# RefOsc10MHz_2V0.net
KiCad netlist of a schematic drawn in EAGLE
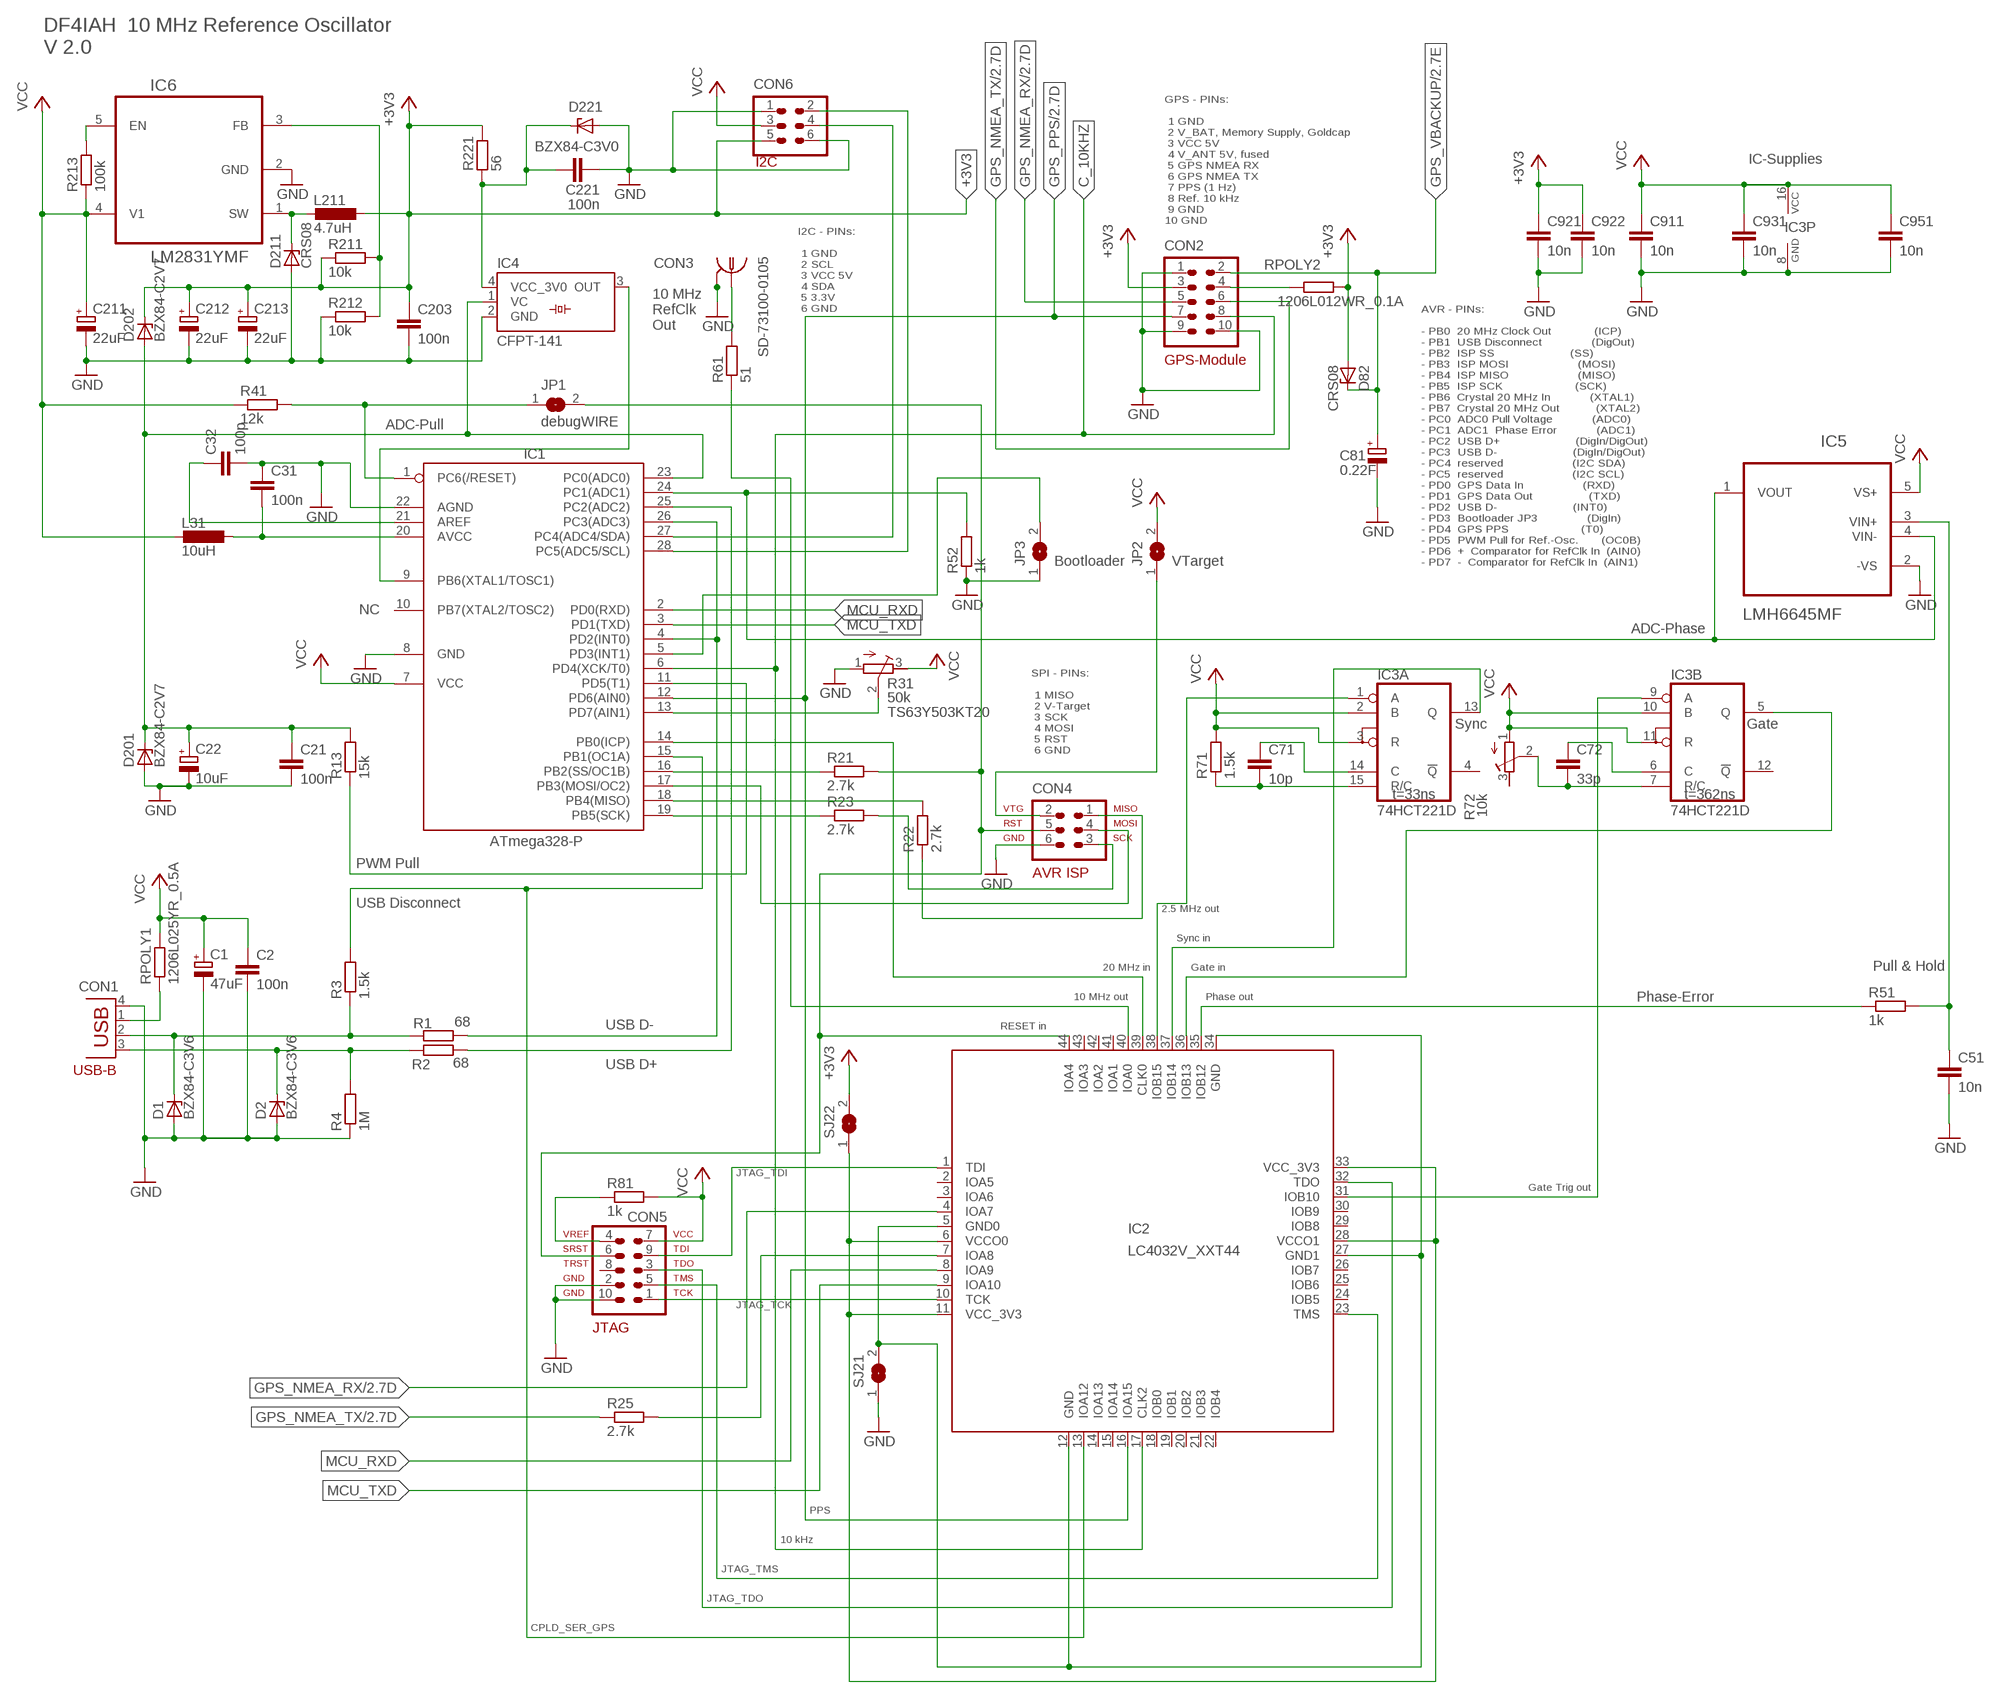
[diagram p0: schematic, sheet 1]
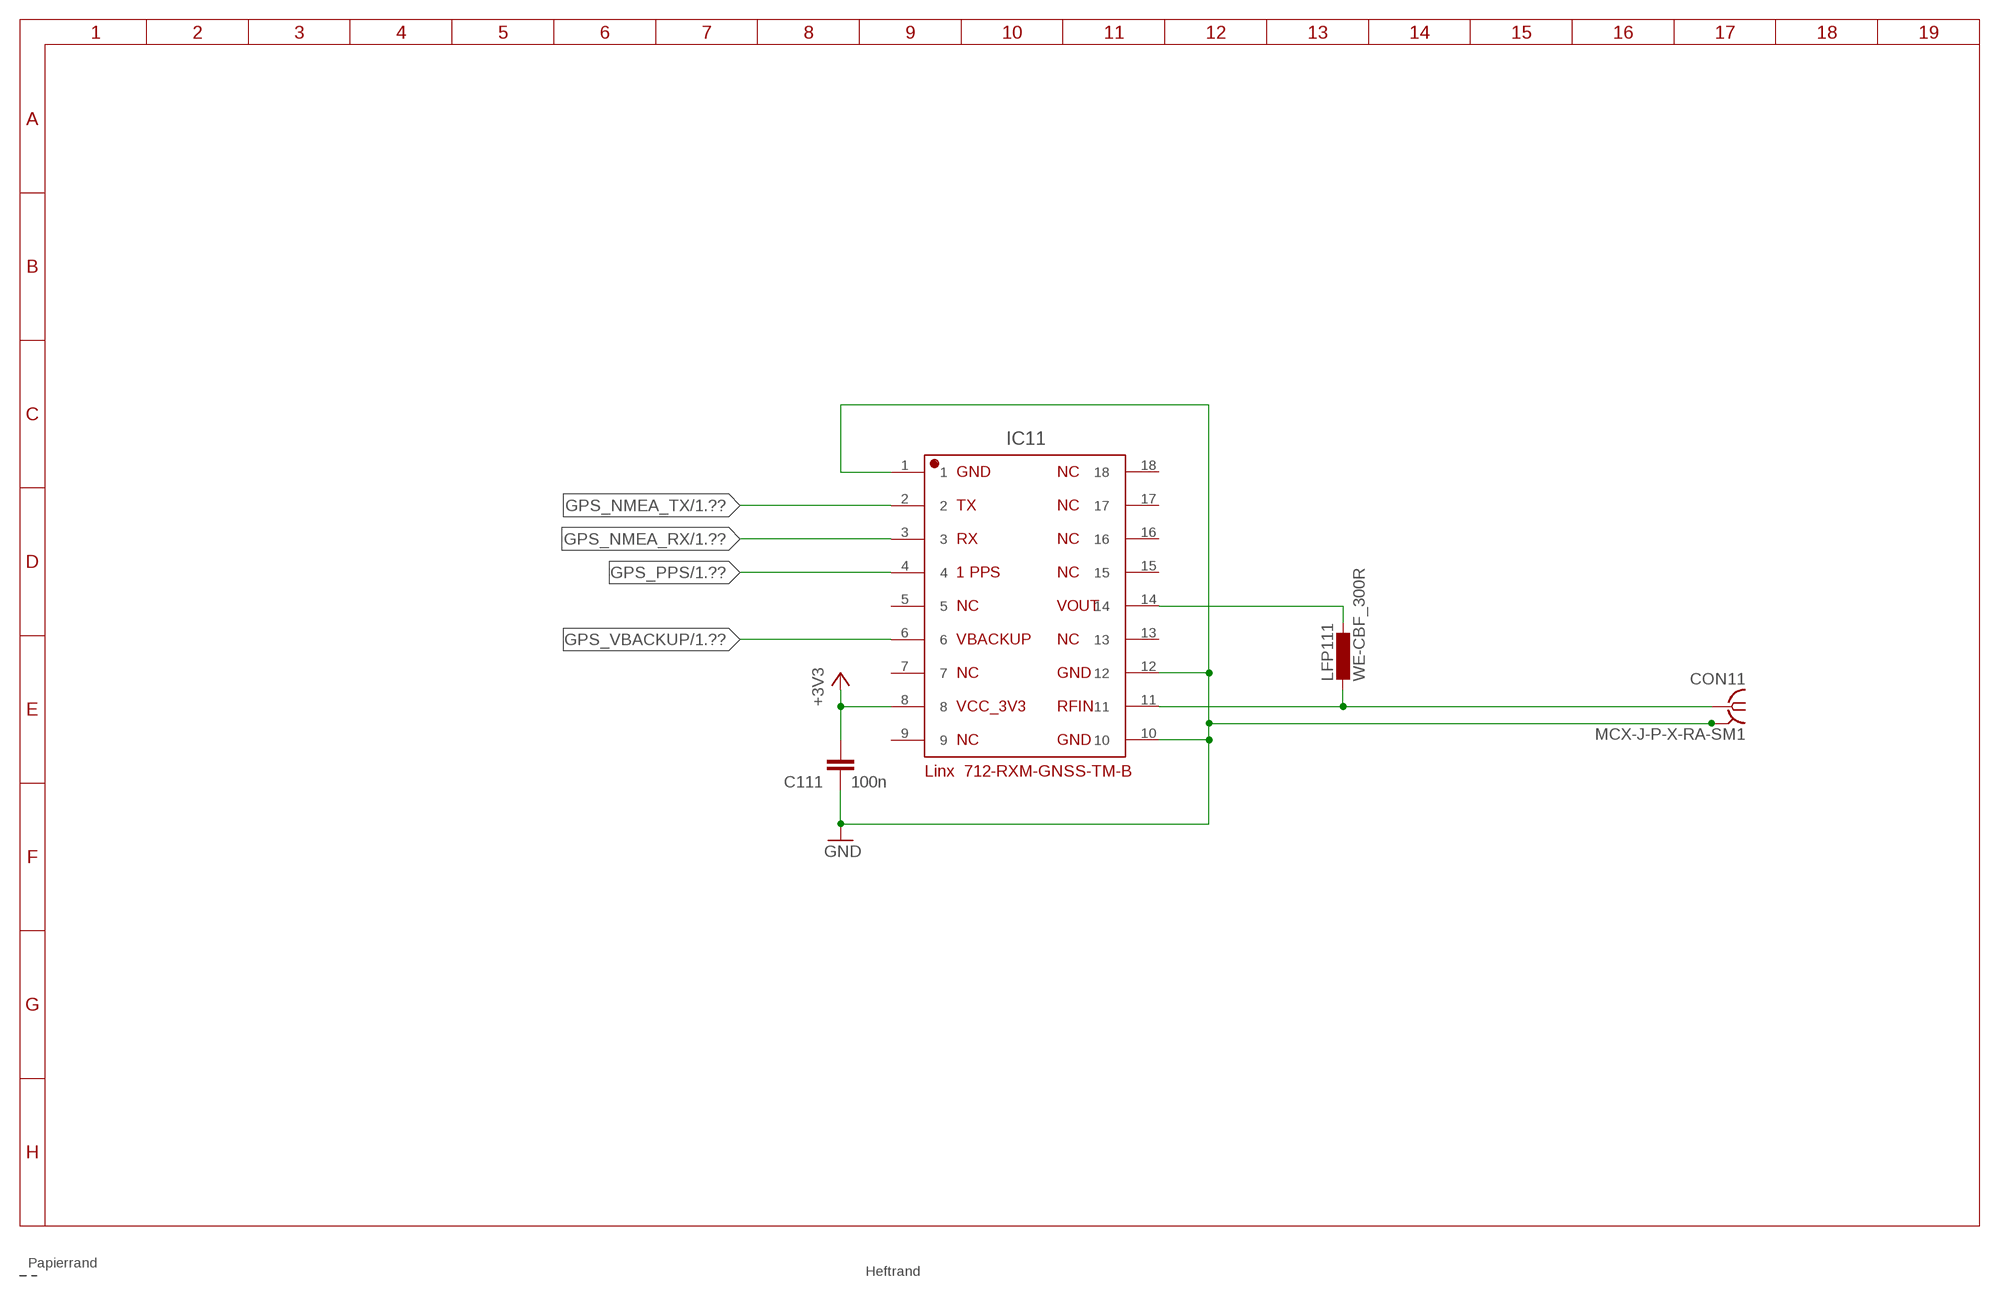
[diagram p1: schematic, sheet 2]

(export (version "E")
  (design (tool "Eeschema 10.0.6"))
  (components
    (comp (ref "C1")
      (value "47uF")
      (footprint "eagle-import:PANASONIC_C")
      (libsource (lib "eagle-import") (part "CPOL-EUC"))
    )
    (comp (ref "C2")
      (value "100n")
      (footprint "eagle-import:C0805")
      (libsource (lib "eagle-import") (part "rcl_C-EUC0805"))
    )
    (comp (ref "C21")
      (value "100n")
      (footprint "eagle-import:C0805")
      (libsource (lib "eagle-import") (part "rcl_C-EUC0805"))
    )
    (comp (ref "C22")
      (value "10uF")
      (footprint "eagle-import:PANASONIC_B")
      (libsource (lib "eagle-import") (part "CPOL-EUB"))
    )
    (comp (ref "C31")
      (value "100n")
      (footprint "eagle-import:C0805")
      (libsource (lib "eagle-import") (part "rcl_C-EUC0805"))
    )
    (comp (ref "C32")
      (value "100p")
      (footprint "eagle-import:C0805")
      (libsource (lib "eagle-import") (part "rcl_C-EUC0805"))
    )
    (comp (ref "C51")
      (value "10n")
      (footprint "eagle-import:C0805")
      (libsource (lib "eagle-import") (part "rcl_C-EUC0805"))
    )
    (comp (ref "C71")
      (value "10p")
      (footprint "eagle-import:C0805")
      (libsource (lib "eagle-import") (part "rcl_C-EUC0805"))
    )
    (comp (ref "C72")
      (value "33p")
      (footprint "eagle-import:C0805")
      (libsource (lib "eagle-import") (part "rcl_C-EUC0805"))
    )
    (comp (ref "C81")
      (value "0.22F")
      (footprint "eagle-import:PANASONIC_C")
      (libsource (lib "eagle-import") (part "CPOL-EUC"))
    )
    (comp (ref "C203")
      (value "100n")
      (footprint "eagle-import:C0805")
      (libsource (lib "eagle-import") (part "rcl_C-EUC0805"))
    )
    (comp (ref "C211")
      (value "22uF")
      (footprint "eagle-import:A_3216-18W")
      (libsource (lib "eagle-import") (part "CPOL-EUA/3216-18W"))
    )
    (comp (ref "C212")
      (value "22uF")
      (footprint "eagle-import:A_3216-18W")
      (libsource (lib "eagle-import") (part "CPOL-EUA/3216-18W"))
    )
    (comp (ref "C213")
      (value "22uF")
      (footprint "eagle-import:A_3216-18W")
      (libsource (lib "eagle-import") (part "CPOL-EUA/3216-18W"))
    )
    (comp (ref "C221")
      (value "100n")
      (footprint "eagle-import:C0805")
      (libsource (lib "eagle-import") (part "rcl_C-EUC0805"))
    )
    (comp (ref "C911")
      (value "10n")
      (footprint "eagle-import:C0805")
      (libsource (lib "eagle-import") (part "rcl_C-EUC0805"))
    )
    (comp (ref "C921")
      (value "10n")
      (footprint "eagle-import:C0805")
      (libsource (lib "eagle-import") (part "rcl_C-EUC0805"))
    )
    (comp (ref "C922")
      (value "10n")
      (footprint "eagle-import:C0805")
      (libsource (lib "eagle-import") (part "rcl_C-EUC0805"))
    )
    (comp (ref "C931")
      (value "10n")
      (footprint "eagle-import:C0805")
      (libsource (lib "eagle-import") (part "rcl_C-EUC0805"))
    )
    (comp (ref "C951")
      (value "10n")
      (footprint "eagle-import:C0805")
      (libsource (lib "eagle-import") (part "rcl_C-EUC0805"))
    )
    (comp (ref "CON1")
      (value "TYCO-AMP_USBUSB-B_SMT")
      (footprint "eagle-import:TYCO-AMP_USB-B_SMT")
      (fields (field (name "MF") "TYCO-AMP") (field (name "MPN") "1734346"))
      (libsource (lib "eagle-import") (part "TYCO-AMP_USBUSB-B_SMT"))
    )
    (comp (ref "CON2")
      (value "HEADER-2X5SMD")
      (footprint "eagle-import:2X5SMD")
      (libsource (lib "eagle-import") (part "HEADER-2X5SMD"))
    )
    (comp (ref "CON3")
      (value "SD-73100-0105")
      (footprint "eagle-import:MOLEX_BNC-JACK-50R_SD-73100-0105")
      (fields (field (name "MF") "MOLEX"))
      (libsource (lib "eagle-import") (part "MOLEX_BNC-JACK-50R_SD-73100-0105"))
    )
    (comp (ref "CON4")
      (value "AVR-ISP-6SMD")
      (footprint "eagle-import:2X3SMD")
      (libsource (lib "eagle-import") (part "AVR-ISP-6SMD"))
    )
    (comp (ref "CON5")
      (value "AVR-JTAG-10SMD")
      (footprint "eagle-import:2X5SMD")
      (libsource (lib "eagle-import") (part "AVR-JTAG-10SMD"))
    )
    (comp (ref "CON6")
      (value "HEADER-2X3SMD")
      (footprint "eagle-import:2X03SMD")
      (libsource (lib "eagle-import") (part "HEADER-2X3SMD"))
    )
    (comp (ref "D1")
      (value "BZX84-C3V6")
      (footprint "eagle-import:TO236")
      (libsource (lib "eagle-import") (part "BZX84CSMD"))
    )
    (comp (ref "D2")
      (value "BZX84-C3V6")
      (footprint "eagle-import:TO236")
      (libsource (lib "eagle-import") (part "BZX84CSMD"))
    )
    (comp (ref "D82")
      (value "CRS08")
      (footprint "eagle-import:SOT23")
      (libsource (lib "eagle-import") (part "ZENER-DIODESOT23"))
    )
    (comp (ref "D201")
      (value "BZX84-C2V7")
      (footprint "eagle-import:TO236")
      (libsource (lib "eagle-import") (part "BZX84CSMD"))
    )
    (comp (ref "D202")
      (value "BZX84-C2V7")
      (footprint "eagle-import:TO236")
      (libsource (lib "eagle-import") (part "BZX84CSMD"))
    )
    (comp (ref "D211")
      (value "CRS08")
      (footprint "eagle-import:SOT23")
      (libsource (lib "eagle-import") (part "ZENER-DIODESOT23"))
    )
    (comp (ref "D221")
      (value "BZX84-C3V0")
      (footprint "eagle-import:TO236")
      (libsource (lib "eagle-import") (part "BZX84CSMD"))
    )
    (comp (ref "IC1")
      (value "ATmega328-P")
      (footprint "eagle-import:DIL28-3")
      (libsource (lib "eagle-import") (part "MEGA8-P"))
    )
    (comp (ref "IC2")
      (value "LC4032V_XXT44")
      (footprint "eagle-import:TQFP44")
      (libsource (lib "eagle-import") (part "LC4032V_XXT44"))
    )
    (comp (ref "IC3")
      (value "74HCT221D")
      (footprint "eagle-import:SO16")
      (libsource (lib "eagle-import") (part "74221DHCT"))
    )
    (comp (ref "IC4")
      (value "CFPT-141")
      (footprint "eagle-import:CFPT-141")
      (fields (field (name "MF") "IQD-FREQUENCY-PRODUCTS") (field (name "MPN") "LFTVXO022175"))
      (libsource (lib "eagle-import") (part "CFPT-141"))
    )
    (comp (ref "IC5")
      (value "LMH6645MF")
      (footprint "eagle-import:SOT95P280X145-5N")
      (libsource (lib "eagle-import") (part "LMH6645MF"))
    )
    (comp (ref "IC6")
      (value "LM2831YMF")
      (footprint "eagle-import:SOT95P280X145-5N")
      (fields (field (name "MPN") "LM2831YMF/NOPB"))
      (libsource (lib "eagle-import") (part "LM2831YMF"))
    )
    (comp (ref "JP1")
      (value "SJW")
      (footprint "eagle-import:SJW")
      (libsource (lib "eagle-import") (part "SJW"))
    )
    (comp (ref "JP2")
      (value "SJW")
      (footprint "eagle-import:SJW")
      (libsource (lib "eagle-import") (part "SJW"))
    )
    (comp (ref "JP3")
      (value "SJW")
      (footprint "eagle-import:SJW")
      (libsource (lib "eagle-import") (part "SJW"))
    )
    (comp (ref "L31")
      (value "10uH")
      (footprint "eagle-import:L1812")
      (libsource (lib "eagle-import") (part "rcl_L-EUL1812"))
    )
    (comp (ref "L211")
      (value "4.7uH")
      (footprint "eagle-import:L5650M")
      (libsource (lib "eagle-import") (part "rcl_L-EUL5650M"))
    )
    (comp (ref "R1")
      (value "68")
      (footprint "eagle-import:R0805")
      (libsource (lib "eagle-import") (part "R-EU_R0805"))
    )
    (comp (ref "R2")
      (value "68")
      (footprint "eagle-import:R0805")
      (libsource (lib "eagle-import") (part "R-EU_R0805"))
    )
    (comp (ref "R3")
      (value "1.5k")
      (footprint "eagle-import:R0805")
      (libsource (lib "eagle-import") (part "R-EU_R0805"))
    )
    (comp (ref "R4")
      (value "1M")
      (footprint "eagle-import:R0805")
      (libsource (lib "eagle-import") (part "R-EU_R0805"))
    )
    (comp (ref "R13")
      (value "15k")
      (footprint "eagle-import:R0805")
      (libsource (lib "eagle-import") (part "R-EU_R0805"))
    )
    (comp (ref "R21")
      (value "2.7k")
      (footprint "eagle-import:R0805")
      (libsource (lib "eagle-import") (part "R-EU_R0805"))
    )
    (comp (ref "R22")
      (value "2.7k")
      (footprint "eagle-import:R0805")
      (libsource (lib "eagle-import") (part "R-EU_R0805"))
    )
    (comp (ref "R23")
      (value "2.7k")
      (footprint "eagle-import:R0805")
      (libsource (lib "eagle-import") (part "R-EU_R0805"))
    )
    (comp (ref "R25")
      (value "2.7k")
      (footprint "eagle-import:R0805")
      (libsource (lib "eagle-import") (part "R-EU_R0805"))
    )
    (comp (ref "R31")
      (value "50k")
      (footprint "eagle-import:RTRIMTS63Y")
      (fields (field (name "NR") "TS63Y503KT20"))
      (libsource (lib "eagle-import") (part "R-TRIMMTS63Y"))
    )
    (comp (ref "R41")
      (value "12k")
      (footprint "eagle-import:R0805")
      (libsource (lib "eagle-import") (part "R-EU_R0805"))
    )
    (comp (ref "R51")
      (value "1k")
      (footprint "eagle-import:R0805")
      (libsource (lib "eagle-import") (part "R-EU_R0805"))
    )
    (comp (ref "R52")
      (value "1k")
      (footprint "eagle-import:R0805")
      (libsource (lib "eagle-import") (part "R-EU_R0805"))
    )
    (comp (ref "R61")
      (value "51")
      (footprint "eagle-import:R0805")
      (libsource (lib "eagle-import") (part "R-EU_R0805"))
    )
    (comp (ref "R71")
      (value "1.5k")
      (footprint "eagle-import:R0805")
      (libsource (lib "eagle-import") (part "R-EU_R0805"))
    )
    (comp (ref "R72")
      (value "10k")
      (footprint "eagle-import:RTRIMTS63Y")
      (libsource (lib "eagle-import") (part "R-TRIMMTS63Y"))
    )
    (comp (ref "R81")
      (value "1k")
      (footprint "eagle-import:R0805")
      (libsource (lib "eagle-import") (part "R-EU_R0805"))
    )
    (comp (ref "R211")
      (value "10k")
      (footprint "eagle-import:R0805")
      (libsource (lib "eagle-import") (part "R-EU_R0805"))
    )
    (comp (ref "R212")
      (value "10k")
      (footprint "eagle-import:R0805")
      (libsource (lib "eagle-import") (part "R-EU_R0805"))
    )
    (comp (ref "R213")
      (value "100k")
      (footprint "eagle-import:R0805")
      (libsource (lib "eagle-import") (part "R-EU_R0805"))
    )
    (comp (ref "R221")
      (value "56")
      (footprint "eagle-import:R0805")
      (libsource (lib "eagle-import") (part "R-EU_R0805"))
    )
    (comp (ref "RPOLY1")
      (value "1206L025YR_0.5A")
      (footprint "eagle-import:M1206")
      (libsource (lib "eagle-import") (part "R-EU_M1206"))
    )
    (comp (ref "RPOLY2")
      (value "1206L012WR_0.1A")
      (footprint "eagle-import:M1206")
      (libsource (lib "eagle-import") (part "R-EU_M1206"))
    )
    (comp (ref "SJ21")
      (value "SJ")
      (footprint "eagle-import:SJ")
      (libsource (lib "eagle-import") (part "SJ"))
    )
    (comp (ref "SJ22")
      (value "SJ")
      (footprint "eagle-import:SJ")
      (libsource (lib "eagle-import") (part "SJ"))
    )
    (comp (ref "C111")
      (value "100n")
      (footprint "eagle-import:C0805")
      (libsource (lib "eagle-import") (part "C-EUC0805"))
    )
    (comp (ref "CON11")
      (value "MCX-J-P-X-RA-SM1")
      (footprint "eagle-import:MCX-J-P-X-RA-SM1")
      (libsource (lib "eagle-import") (part "MCX-J-P-X-RA-SM1"))
    )
    (comp (ref "IC11")
      (value "712-RXM-GNSS-TM-B")
      (footprint "eagle-import:712-RXM-GNSS-TM-B")
      (libsource (lib "eagle-import") (part "712-RXM-GNSS-TM-B"))
    )
    (comp (ref "LFP111")
      (value "WE-CBF_300R")
      (footprint "eagle-import:L3216C")
      (libsource (lib "eagle-import") (part "L-EUL3216C"))
    )
  )
  (nets
    (net (code "1") (name "+3V3") (class "Default")
      (node (ref "C111") (pin "1") (pinfunction "1_1") (pintype "passive"))
      (node (ref "C203") (pin "1") (pinfunction "1_1") (pintype "passive"))
      (node (ref "C212") (pin "+") (pinfunction "+_+") (pintype "passive"))
      (node (ref "C213") (pin "+") (pinfunction "+_+") (pintype "passive"))
      (node (ref "C921") (pin "1") (pinfunction "1_1") (pintype "passive"))
      (node (ref "C922") (pin "1") (pinfunction "1_1") (pintype "passive"))
      (node (ref "CON2") (pin "3") (pinfunction "3_3") (pintype "passive"))
      (node (ref "CON6") (pin "5") (pinfunction "5_5") (pintype "passive"))
      (node (ref "D202") (pin "C") (pinfunction "C_C") (pintype "passive"))
      (node (ref "D82") (pin "1") (pinfunction "A_1") (pintype "passive"))
      (node (ref "IC11") (pin "8") (pinfunction "8_8") (pintype "power_in"))
      (node (ref "L211") (pin "1") (pinfunction "1_1") (pintype "passive"))
      (node (ref "R211") (pin "1") (pinfunction "1_1") (pintype "passive"))
      (node (ref "R221") (pin "1") (pinfunction "1_1") (pintype "passive"))
      (node (ref "RPOLY2") (pin "2") (pinfunction "2_2") (pintype "passive"))
      (node (ref "SJ22") (pin "2") (pinfunction "2_2") (pintype "passive"))
    )
    (net (code "2") (name "C_10KHZ") (class "Default")
      (node (ref "CON2") (pin "8") (pinfunction "8_8") (pintype "passive"))
      (node (ref "IC1") (pin "6") (pinfunction "PD4(XCK/T0)_6") (pintype "bidirectional"))
      (node (ref "IC2") (pin "17") (pinfunction "CLK2_17") (pintype "input"))
    )
    (net (code "3") (name "GND") (class "Default")
      (node (ref "C1") (pin "-") (pinfunction "-_-") (pintype "passive"))
      (node (ref "C111") (pin "2") (pinfunction "2_2") (pintype "passive"))
      (node (ref "C2") (pin "2") (pinfunction "2_2") (pintype "passive"))
      (node (ref "C203") (pin "2") (pinfunction "2_2") (pintype "passive"))
      (node (ref "C21") (pin "2") (pinfunction "2_2") (pintype "passive"))
      (node (ref "C211") (pin "-") (pinfunction "-_-") (pintype "passive"))
      (node (ref "C212") (pin "-") (pinfunction "-_-") (pintype "passive"))
      (node (ref "C213") (pin "-") (pinfunction "-_-") (pintype "passive"))
      (node (ref "C22") (pin "-") (pinfunction "-_-") (pintype "passive"))
      (node (ref "C221") (pin "2") (pinfunction "2_2") (pintype "passive"))
      (node (ref "C31") (pin "1") (pinfunction "1_1") (pintype "passive"))
      (node (ref "C32") (pin "2") (pinfunction "2_2") (pintype "passive"))
      (node (ref "C51") (pin "2") (pinfunction "2_2") (pintype "passive"))
      (node (ref "C81") (pin "-") (pinfunction "-_-") (pintype "passive"))
      (node (ref "C911") (pin "2") (pinfunction "2_2") (pintype "passive"))
      (node (ref "C921") (pin "2") (pinfunction "2_2") (pintype "passive"))
      (node (ref "C922") (pin "2") (pinfunction "2_2") (pintype "passive"))
      (node (ref "C931") (pin "2") (pinfunction "2_2") (pintype "passive"))
      (node (ref "C951") (pin "2") (pinfunction "2_2") (pintype "passive"))
      (node (ref "CON1") (pin "4") (pinfunction "GND_4") (pintype "bidirectional"))
      (node (ref "CON11") (pin "2") (pinfunction "2_2") (pintype "passive"))
      (node (ref "CON11") (pin "3") (pinfunction "3_3") (pintype "passive"))
      (node (ref "CON11") (pin "4") (pinfunction "4_4") (pintype "passive"))
      (node (ref "CON11") (pin "5") (pinfunction "5_5") (pintype "passive"))
      (node (ref "CON2") (pin "1") (pinfunction "1_1") (pintype "passive"))
      (node (ref "CON2") (pin "10") (pinfunction "10_10") (pintype "passive"))
      (node (ref "CON2") (pin "9") (pinfunction "9_9") (pintype "passive"))
      (node (ref "CON3") (pin "2") (pinfunction "2_2") (pintype "passive"))
      (node (ref "CON3") (pin "3") (pinfunction "3_3") (pintype "passive"))
      (node (ref "CON4") (pin "6") (pinfunction "6_6") (pintype "passive"))
      (node (ref "CON5") (pin "10") (pinfunction "10_10") (pintype "passive"))
      (node (ref "CON5") (pin "2") (pinfunction "2_2") (pintype "passive"))
      (node (ref "CON6") (pin "1") (pinfunction "1_1") (pintype "passive"))
      (node (ref "CON6") (pin "6") (pinfunction "6_6") (pintype "passive"))
      (node (ref "D1") (pin "A") (pinfunction "A_A") (pintype "passive"))
      (node (ref "D2") (pin "A") (pinfunction "A_A") (pintype "passive"))
      (node (ref "D201") (pin "A") (pinfunction "A_A") (pintype "passive"))
      (node (ref "D211") (pin "1") (pinfunction "A_1") (pintype "passive"))
      (node (ref "D221") (pin "A") (pinfunction "A_A") (pintype "passive"))
      (node (ref "IC1") (pin "22") (pinfunction "AGND_22") (pintype "bidirectional"))
      (node (ref "IC1") (pin "8") (pinfunction "GND_8") (pintype "bidirectional"))
      (node (ref "IC11") (pin "1") (pinfunction "1_1") (pintype "power_in"))
      (node (ref "IC11") (pin "10") (pinfunction "10_10") (pintype "power_in"))
      (node (ref "IC11") (pin "12") (pinfunction "12_12") (pintype "power_in"))
      (node (ref "IC3") (pin "8") (pinfunction "GND_8") (pintype "power_in"))
      (node (ref "IC4") (pin "2") (pinfunction "GND_2") (pintype "power_in"))
      (node (ref "IC5") (pin "2") (pinfunction "-VS_2") (pintype "power_in"))
      (node (ref "IC6") (pin "2") (pinfunction "GND_2") (pintype "power_in"))
      (node (ref "JP3") (pin "1") (pinfunction "1_1") (pintype "passive"))
      (node (ref "R212") (pin "1") (pinfunction "1_1") (pintype "passive"))
      (node (ref "R31") (pin "1") (pinfunction "A_1") (pintype "passive"))
      (node (ref "R4") (pin "1") (pinfunction "1_1") (pintype "passive"))
      (node (ref "R52") (pin "1") (pinfunction "1_1") (pintype "passive"))
      (node (ref "SJ21") (pin "1") (pinfunction "1_1") (pintype "passive"))
    )
    (net (code "4") (name "GPS_NMEA_RX") (class "Default")
      (node (ref "CON2") (pin "5") (pinfunction "5_5") (pintype "passive"))
      (node (ref "IC11") (pin "3") (pinfunction "3_3") (pintype "output"))
      (node (ref "IC2") (pin "4") (pinfunction "IOA7_4") (pintype "bidirectional"))
    )
    (net (code "5") (name "GPS_NMEA_TX") (class "Default")
      (node (ref "CON2") (pin "6") (pinfunction "6_6") (pintype "passive"))
      (node (ref "IC11") (pin "2") (pinfunction "2_2") (pintype "input"))
      (node (ref "R25") (pin "1") (pinfunction "1_1") (pintype "passive"))
    )
    (net (code "6") (name "GPS_PPS") (class "Default")
      (node (ref "CON2") (pin "7") (pinfunction "7_7") (pintype "passive"))
      (node (ref "IC1") (pin "12") (pinfunction "PD6(AIN0)_12") (pintype "bidirectional"))
      (node (ref "IC11") (pin "4") (pinfunction "4_4") (pintype "output"))
      (node (ref "IC2") (pin "16") (pinfunction "IOA15_16") (pintype "bidirectional"))
    )
    (net (code "7") (name "GPS_VBACKUP") (class "Default")
      (node (ref "C81") (pin "+") (pinfunction "+_+") (pintype "passive"))
      (node (ref "CON2") (pin "2") (pinfunction "2_2") (pintype "passive"))
      (node (ref "D82") (pin "3") (pinfunction "C_3") (pintype "passive"))
      (node (ref "IC11") (pin "6") (pinfunction "6_6") (pintype "power_in"))
    )
    (net (code "8") (name "MCU_RXD") (class "Default")
      (node (ref "IC1") (pin "2") (pinfunction "PD0(RXD)_2") (pintype "bidirectional"))
      (node (ref "IC2") (pin "8") (pinfunction "IOA9_8") (pintype "bidirectional"))
    )
    (net (code "9") (name "MCU_TXD") (class "Default")
      (node (ref "IC1") (pin "3") (pinfunction "PD1(TXD)_3") (pintype "bidirectional"))
      (node (ref "IC2") (pin "9") (pinfunction "IOA10_9") (pintype "bidirectional"))
    )
    (net (code "10") (name "Net-(CON1-D+)") (class "Default")
      (node (ref "CON1") (pin "3") (pinfunction "D+_3") (pintype "bidirectional"))
      (node (ref "D2") (pin "C") (pinfunction "C_C") (pintype "passive"))
      (node (ref "R2") (pin "1") (pinfunction "1_1") (pintype "passive"))
      (node (ref "R4") (pin "2") (pinfunction "2_2") (pintype "passive"))
    )
    (net (code "11") (name "Net-(CON1-D-)") (class "Default")
      (node (ref "CON1") (pin "2") (pinfunction "D-_2") (pintype "bidirectional"))
      (node (ref "D1") (pin "C") (pinfunction "C_C") (pintype "passive"))
      (node (ref "R1") (pin "1") (pinfunction "1_1") (pintype "passive"))
      (node (ref "R3") (pin "1") (pinfunction "1_1") (pintype "passive"))
    )
    (net (code "12") (name "Net-(CON1-VBUS)") (class "Default")
      (node (ref "CON1") (pin "1") (pinfunction "VBUS_1") (pintype "bidirectional"))
      (node (ref "RPOLY1") (pin "1") (pinfunction "1_1") (pintype "passive"))
    )
    (net (code "13") (name "Net-(CON2-Pad4)") (class "Default")
      (node (ref "CON2") (pin "4") (pinfunction "4_4") (pintype "passive"))
      (node (ref "RPOLY2") (pin "1") (pinfunction "1_1") (pintype "passive"))
    )
    (net (code "14") (name "Net-(CON3-Pad1)") (class "Default")
      (node (ref "CON3") (pin "1") (pinfunction "1_1") (pintype "passive"))
      (node (ref "R61") (pin "2") (pinfunction "2_2") (pintype "passive"))
    )
    (net (code "15") (name "Net-(CON4-Pad1)") (class "Default")
      (node (ref "CON4") (pin "1") (pinfunction "1_1") (pintype "passive"))
      (node (ref "R22") (pin "1") (pinfunction "1_1") (pintype "passive"))
    )
    (net (code "16") (name "Net-(CON4-Pad2)") (class "Default")
      (node (ref "CON4") (pin "2") (pinfunction "2_2") (pintype "passive"))
      (node (ref "JP2") (pin "1") (pinfunction "1_1") (pintype "passive"))
    )
    (net (code "17") (name "Net-(CON4-Pad3)") (class "Default")
      (node (ref "CON4") (pin "3") (pinfunction "3_3") (pintype "passive"))
      (node (ref "R23") (pin "2") (pinfunction "2_2") (pintype "passive"))
    )
    (net (code "18") (name "Net-(CON5-Pad4)") (class "Default")
      (node (ref "CON5") (pin "4") (pinfunction "4_4") (pintype "passive"))
      (node (ref "R81") (pin "1") (pinfunction "1_1") (pintype "passive"))
    )
    (net (code "19") (name "Net-(CON11-Pad1)") (class "Default")
      (node (ref "CON11") (pin "1") (pinfunction "1_1") (pintype "passive"))
      (node (ref "IC11") (pin "11") (pinfunction "11_11") (pintype "input"))
      (node (ref "LFP111") (pin "2") (pinfunction "2_2") (pintype "passive"))
    )
    (net (code "20") (name "Net-(D211-C)") (class "Default")
      (node (ref "D211") (pin "3") (pinfunction "C_3") (pintype "passive"))
      (node (ref "IC6") (pin "1") (pinfunction "SW_1") (pintype "output"))
      (node (ref "L211") (pin "2") (pinfunction "2_2") (pintype "passive"))
    )
    (net (code "21") (name "Net-(IC1-AREF)") (class "Default")
      (node (ref "C32") (pin "1") (pinfunction "1_1") (pintype "passive"))
      (node (ref "IC1") (pin "21") (pinfunction "AREF_21") (pintype "bidirectional"))
    )
    (net (code "22") (name "Net-(IC1-AVCC)") (class "Default")
      (node (ref "C31") (pin "2") (pinfunction "2_2") (pintype "passive"))
      (node (ref "IC1") (pin "20") (pinfunction "AVCC_20") (pintype "bidirectional"))
      (node (ref "L31") (pin "1") (pinfunction "1_1") (pintype "passive"))
    )
    (net (code "23") (name "Net-(IC1-PB0(ICP))") (class "Default")
      (node (ref "IC1") (pin "14") (pinfunction "PB0(ICP)_14") (pintype "bidirectional"))
      (node (ref "IC2") (pin "39") (pinfunction "CLK0_39") (pintype "input"))
    )
    (net (code "24") (name "Net-(IC1-PB1(OC1A))") (class "Default")
      (node (ref "IC1") (pin "15") (pinfunction "PB1(OC1A)_15") (pintype "bidirectional"))
      (node (ref "IC2") (pin "13") (pinfunction "IOA12_13") (pintype "bidirectional"))
      (node (ref "R3") (pin "2") (pinfunction "2_2") (pintype "passive"))
    )
    (net (code "25") (name "Net-(IC1-PB2(SS{slash}OC1B))") (class "Default")
      (node (ref "IC1") (pin "16") (pinfunction "PB2(SS/OC1B)_16") (pintype "bidirectional"))
      (node (ref "R21") (pin "1") (pinfunction "1_1") (pintype "passive"))
    )
    (net (code "26") (name "Net-(IC1-PB3(MOSI{slash}OC2))") (class "Default")
      (node (ref "CON4") (pin "4") (pinfunction "4_4") (pintype "passive"))
      (node (ref "IC1") (pin "17") (pinfunction "PB3(MOSI/OC2)_17") (pintype "bidirectional"))
    )
    (net (code "27") (name "Net-(IC1-PB4(MISO))") (class "Default")
      (node (ref "IC1") (pin "18") (pinfunction "PB4(MISO)_18") (pintype "bidirectional"))
      (node (ref "R22") (pin "2") (pinfunction "2_2") (pintype "passive"))
    )
    (net (code "28") (name "Net-(IC1-PB5(SCK))") (class "Default")
      (node (ref "IC1") (pin "19") (pinfunction "PB5(SCK)_19") (pintype "bidirectional"))
      (node (ref "R23") (pin "1") (pinfunction "1_1") (pintype "passive"))
    )
    (net (code "29") (name "Net-(IC1-PB6(XTAL1{slash}TOSC1))") (class "Default")
      (node (ref "IC1") (pin "9") (pinfunction "PB6(XTAL1/TOSC1)_9") (pintype "bidirectional"))
      (node (ref "IC4") (pin "3") (pinfunction "OUT_3") (pintype "output"))
    )
    (net (code "30") (name "Net-(IC1-PC0(ADC0))") (class "Default")
      (node (ref "C21") (pin "1") (pinfunction "1_1") (pintype "passive"))
      (node (ref "C22") (pin "+") (pinfunction "+_+") (pintype "passive"))
      (node (ref "D201") (pin "C") (pinfunction "C_C") (pintype "passive"))
      (node (ref "D202") (pin "A") (pinfunction "A_A") (pintype "passive"))
      (node (ref "IC1") (pin "23") (pinfunction "PC0(ADC0)_23") (pintype "bidirectional"))
      (node (ref "IC4") (pin "1") (pinfunction "VC_1") (pintype "input"))
      (node (ref "R13") (pin "2") (pinfunction "2_2") (pintype "passive"))
    )
    (net (code "31") (name "Net-(IC1-PC1(ADC1))") (class "Default")
      (node (ref "IC1") (pin "24") (pinfunction "PC1(ADC1)_24") (pintype "bidirectional"))
      (node (ref "IC5") (pin "1") (pinfunction "VOUT_1") (pintype "output"))
      (node (ref "IC5") (pin "4") (pinfunction "VIN-_4") (pintype "input"))
      (node (ref "R52") (pin "2") (pinfunction "2_2") (pintype "passive"))
    )
    (net (code "32") (name "Net-(IC1-PC2(ADC2))") (class "Default")
      (node (ref "IC1") (pin "25") (pinfunction "PC2(ADC2)_25") (pintype "bidirectional"))
      (node (ref "R2") (pin "2") (pinfunction "2_2") (pintype "passive"))
    )
    (net (code "33") (name "Net-(IC1-PC3(ADC3))") (class "Default")
      (node (ref "IC1") (pin "26") (pinfunction "PC3(ADC3)_26") (pintype "bidirectional"))
      (node (ref "IC1") (pin "4") (pinfunction "PD2(INT0)_4") (pintype "bidirectional"))
      (node (ref "R1") (pin "2") (pinfunction "2_2") (pintype "passive"))
    )
    (net (code "34") (name "Net-(IC1-PC4(ADC4{slash}SDA))") (class "Default")
      (node (ref "CON6") (pin "4") (pinfunction "4_4") (pintype "passive"))
      (node (ref "IC1") (pin "27") (pinfunction "PC4(ADC4/SDA)_27") (pintype "bidirectional"))
    )
    (net (code "35") (name "Net-(IC1-PC5(ADC5{slash}SCL))") (class "Default")
      (node (ref "CON6") (pin "2") (pinfunction "2_2") (pintype "passive"))
      (node (ref "IC1") (pin "28") (pinfunction "PC5(ADC5/SCL)_28") (pintype "bidirectional"))
    )
    (net (code "36") (name "Net-(IC1-PC6({slash}RESET))") (class "Default")
      (node (ref "IC1") (pin "1") (pinfunction "PC6(/RESET)_1") (pintype "bidirectional"))
      (node (ref "JP1") (pin "1") (pinfunction "1_1") (pintype "passive"))
      (node (ref "R41") (pin "2") (pinfunction "2_2") (pintype "passive"))
    )
    (net (code "37") (name "Net-(IC1-PD3(INT1))") (class "Default")
      (node (ref "IC1") (pin "5") (pinfunction "PD3(INT1)_5") (pintype "bidirectional"))
      (node (ref "JP3") (pin "2") (pinfunction "2_2") (pintype "passive"))
    )
    (net (code "38") (name "Net-(IC1-PD5(T1))") (class "Default")
      (node (ref "IC1") (pin "11") (pinfunction "PD5(T1)_11") (pintype "bidirectional"))
      (node (ref "R13") (pin "1") (pinfunction "1_1") (pintype "passive"))
    )
    (net (code "39") (name "Net-(IC1-PD7(AIN1))") (class "Default")
      (node (ref "IC1") (pin "13") (pinfunction "PD7(AIN1)_13") (pintype "bidirectional"))
      (node (ref "R31") (pin "2") (pinfunction "S_2") (pintype "passive"))
    )
    (net (code "40") (name "Net-(IC2-GND0)") (class "Default")
      (node (ref "IC2") (pin "12") (pinfunction "GND_12") (pintype "power_in"))
      (node (ref "IC2") (pin "27") (pinfunction "GND1_27") (pintype "power_in"))
      (node (ref "IC2") (pin "34") (pinfunction "GND_34") (pintype "power_in"))
      (node (ref "IC2") (pin "5") (pinfunction "GND0_5") (pintype "power_in"))
      (node (ref "SJ21") (pin "2") (pinfunction "2_2") (pintype "passive"))
    )
    (net (code "41") (name "Net-(IC2-IOA0)") (class "Default")
      (node (ref "IC2") (pin "40") (pinfunction "IOA0_40") (pintype "bidirectional"))
      (node (ref "R61") (pin "1") (pinfunction "1_1") (pintype "passive"))
    )
    (net (code "42") (name "Net-(IC2-IOA4)") (class "Default")
      (node (ref "CON4") (pin "5") (pinfunction "5_5") (pintype "passive"))
      (node (ref "CON5") (pin "6") (pinfunction "6_6") (pintype "passive"))
      (node (ref "IC2") (pin "44") (pinfunction "IOA4_44") (pintype "bidirectional"))
      (node (ref "JP1") (pin "2") (pinfunction "2_2") (pintype "passive"))
      (node (ref "R21") (pin "2") (pinfunction "2_2") (pintype "passive"))
    )
    (net (code "43") (name "Net-(IC2-IOA8)") (class "Default")
      (node (ref "IC2") (pin "7") (pinfunction "IOA8_7") (pintype "bidirectional"))
      (node (ref "R25") (pin "2") (pinfunction "2_2") (pintype "passive"))
    )
    (net (code "44") (name "Net-(IC2-IOB10)") (class "Default")
      (node (ref "IC2") (pin "31") (pinfunction "IOB10_31") (pintype "bidirectional"))
      (node (ref "IC3") (pin "9") (pinfunction "A_9") (pintype "input"))
    )
    (net (code "45") (name "Net-(IC2-IOB12)") (class "Default")
      (node (ref "IC2") (pin "35") (pinfunction "IOB12_35") (pintype "bidirectional"))
      (node (ref "R51") (pin "1") (pinfunction "1_1") (pintype "passive"))
    )
    (net (code "46") (name "Net-(IC2-IOB13)") (class "Default")
      (node (ref "IC2") (pin "36") (pinfunction "IOB13_36") (pintype "bidirectional"))
      (node (ref "IC3") (pin "5") (pinfunction "Q_5") (pintype "output"))
    )
    (net (code "47") (name "Net-(IC2-IOB14)") (class "Default")
      (node (ref "IC2") (pin "37") (pinfunction "IOB14_37") (pintype "bidirectional"))
      (node (ref "IC3") (pin "13") (pinfunction "Q_13") (pintype "output"))
    )
    (net (code "48") (name "Net-(IC2-IOB15)") (class "Default")
      (node (ref "IC2") (pin "38") (pinfunction "IOB15_38") (pintype "bidirectional"))
      (node (ref "IC3") (pin "1") (pinfunction "A_1") (pintype "input"))
    )
    (net (code "49") (name "Net-(IC2-TCK)") (class "Default")
      (node (ref "CON5") (pin "1") (pinfunction "1_1") (pintype "passive"))
      (node (ref "IC2") (pin "10") (pinfunction "TCK_10") (pintype "input"))
    )
    (net (code "50") (name "Net-(IC2-TDI)") (class "Default")
      (node (ref "CON5") (pin "9") (pinfunction "9_9") (pintype "passive"))
      (node (ref "IC2") (pin "1") (pinfunction "TDI_1") (pintype "input"))
    )
    (net (code "51") (name "Net-(IC2-TDO)") (class "Default")
      (node (ref "CON5") (pin "3") (pinfunction "3_3") (pintype "passive"))
      (node (ref "IC2") (pin "32") (pinfunction "TDO_32") (pintype "output"))
    )
    (net (code "52") (name "Net-(IC2-TMS)") (class "Default")
      (node (ref "CON5") (pin "5") (pinfunction "5_5") (pintype "passive"))
      (node (ref "IC2") (pin "23") (pinfunction "TMS_23") (pintype "input"))
    )
    (net (code "53") (name "Net-(IC2-VCCO0)") (class "Default")
      (node (ref "IC2") (pin "11") (pinfunction "VCC_3V3_11") (pintype "power_in"))
      (node (ref "IC2") (pin "28") (pinfunction "VCCO1_28") (pintype "power_in"))
      (node (ref "IC2") (pin "33") (pinfunction "VCC_3V3_33") (pintype "power_in"))
      (node (ref "IC2") (pin "6") (pinfunction "VCCO0_6") (pintype "power_in"))
      (node (ref "SJ22") (pin "1") (pinfunction "1_1") (pintype "passive"))
    )
    (net (code "54") (name "Net-(IC3A-C)") (class "Default")
      (node (ref "C71") (pin "1") (pinfunction "1_1") (pintype "passive"))
      (node (ref "IC3") (pin "14") (pinfunction "C_14") (pintype "input"))
    )
    (net (code "55") (name "Net-(IC3A-R{slash}C)") (class "Default")
      (node (ref "C71") (pin "2") (pinfunction "2_2") (pintype "passive"))
      (node (ref "IC3") (pin "15") (pinfunction "R/C_15") (pintype "input"))
      (node (ref "R71") (pin "1") (pinfunction "1_1") (pintype "passive"))
    )
    (net (code "56") (name "Net-(IC3B-C)") (class "Default")
      (node (ref "C72") (pin "1") (pinfunction "1_1") (pintype "passive"))
      (node (ref "IC3") (pin "6") (pinfunction "C_6") (pintype "input"))
    )
    (net (code "57") (name "Net-(IC3B-R{slash}C)") (class "Default")
      (node (ref "C72") (pin "2") (pinfunction "2_2") (pintype "passive"))
      (node (ref "IC3") (pin "7") (pinfunction "R/C_7") (pintype "input"))
      (node (ref "R72") (pin "2") (pinfunction "S_2") (pintype "passive"))
    )
    (net (code "58") (name "Net-(IC4-VCC_3V0)") (class "Default")
      (node (ref "C221") (pin "1") (pinfunction "1_1") (pintype "passive"))
      (node (ref "D221") (pin "C") (pinfunction "C_C") (pintype "passive"))
      (node (ref "IC4") (pin "4") (pinfunction "VCC_3V0_4") (pintype "power_in"))
      (node (ref "R221") (pin "2") (pinfunction "2_2") (pintype "passive"))
    )
    (net (code "59") (name "Net-(IC5-VIN+)") (class "Default")
      (node (ref "C51") (pin "1") (pinfunction "1_1") (pintype "passive"))
      (node (ref "IC5") (pin "3") (pinfunction "VIN+_3") (pintype "input"))
      (node (ref "R51") (pin "2") (pinfunction "2_2") (pintype "passive"))
    )
    (net (code "60") (name "Net-(IC6-EN)") (class "Default")
      (node (ref "IC6") (pin "5") (pinfunction "EN_5") (pintype "input"))
      (node (ref "R213") (pin "2") (pinfunction "2_2") (pintype "passive"))
    )
    (net (code "61") (name "Net-(IC6-FB)") (class "Default")
      (node (ref "IC6") (pin "3") (pinfunction "FB_3") (pintype "input"))
      (node (ref "R211") (pin "2") (pinfunction "2_2") (pintype "passive"))
      (node (ref "R212") (pin "2") (pinfunction "2_2") (pintype "passive"))
    )
    (net (code "62") (name "Net-(IC11-Pad14)") (class "Default")
      (node (ref "IC11") (pin "14") (pinfunction "14_14") (pintype "power_in"))
      (node (ref "LFP111") (pin "1") (pinfunction "1_1") (pintype "passive"))
    )
    (net (code "63") (name "VCC") (class "Default")
      (node (ref "C1") (pin "+") (pinfunction "+_+") (pintype "passive"))
      (node (ref "C2") (pin "1") (pinfunction "1_1") (pintype "passive"))
      (node (ref "C211") (pin "+") (pinfunction "+_+") (pintype "passive"))
      (node (ref "C911") (pin "1") (pinfunction "1_1") (pintype "passive"))
      (node (ref "C931") (pin "1") (pinfunction "1_1") (pintype "passive"))
      (node (ref "C951") (pin "1") (pinfunction "1_1") (pintype "passive"))
      (node (ref "CON5") (pin "7") (pinfunction "7_7") (pintype "passive"))
      (node (ref "CON6") (pin "3") (pinfunction "3_3") (pintype "passive"))
      (node (ref "IC1") (pin "7") (pinfunction "VCC_7") (pintype "bidirectional"))
      (node (ref "IC3") (pin "10") (pinfunction "B_10") (pintype "input"))
      (node (ref "IC3") (pin "11") (pinfunction "R_11") (pintype "input"))
      (node (ref "IC3") (pin "16") (pinfunction "VCC_16") (pintype "power_in"))
      (node (ref "IC3") (pin "2") (pinfunction "B_2") (pintype "input"))
      (node (ref "IC3") (pin "3") (pinfunction "R_3") (pintype "input"))
      (node (ref "IC5") (pin "5") (pinfunction "VS+_5") (pintype "power_in"))
      (node (ref "IC6") (pin "4") (pinfunction "V1_4") (pintype "power_in"))
      (node (ref "JP2") (pin "2") (pinfunction "2_2") (pintype "passive"))
      (node (ref "L31") (pin "2") (pinfunction "2_2") (pintype "passive"))
      (node (ref "R213") (pin "1") (pinfunction "1_1") (pintype "passive"))
      (node (ref "R31") (pin "3") (pinfunction "E_3") (pintype "passive"))
      (node (ref "R41") (pin "1") (pinfunction "1_1") (pintype "passive"))
      (node (ref "R71") (pin "2") (pinfunction "2_2") (pintype "passive"))
      (node (ref "R72") (pin "1") (pinfunction "A_1") (pintype "passive"))
      (node (ref "R81") (pin "2") (pinfunction "2_2") (pintype "passive"))
      (node (ref "RPOLY1") (pin "2") (pinfunction "2_2") (pintype "passive"))
    )
    (net (code "64") (name "unconnected-(CON5-Pad8)") (class "Default")
      (node (ref "CON5") (pin "8") (pinfunction "8_8") (pintype "passive"))
    )
    (net (code "65") (name "unconnected-(IC1-PB7(XTAL2{slash}TOSC2)-Pad10)") (class "Default")
      (node (ref "IC1") (pin "10") (pinfunction "PB7(XTAL2/TOSC2)_10") (pintype "bidirectional"))
    )
    (net (code "66") (name "unconnected-(IC2-IOA1-Pad41)") (class "Default")
      (node (ref "IC2") (pin "41") (pinfunction "IOA1_41") (pintype "bidirectional"))
    )
    (net (code "67") (name "unconnected-(IC2-IOA2-Pad42)") (class "Default")
      (node (ref "IC2") (pin "42") (pinfunction "IOA2_42") (pintype "bidirectional"))
    )
    (net (code "68") (name "unconnected-(IC2-IOA3-Pad43)") (class "Default")
      (node (ref "IC2") (pin "43") (pinfunction "IOA3_43") (pintype "bidirectional"))
    )
    (net (code "69") (name "unconnected-(IC2-IOA5-Pad2)") (class "Default")
      (node (ref "IC2") (pin "2") (pinfunction "IOA5_2") (pintype "bidirectional"))
    )
    (net (code "70") (name "unconnected-(IC2-IOA6-Pad3)") (class "Default")
      (node (ref "IC2") (pin "3") (pinfunction "IOA6_3") (pintype "bidirectional"))
    )
    (net (code "71") (name "unconnected-(IC2-IOA13-Pad14)") (class "Default")
      (node (ref "IC2") (pin "14") (pinfunction "IOA13_14") (pintype "bidirectional"))
    )
    (net (code "72") (name "unconnected-(IC2-IOA14-Pad15)") (class "Default")
      (node (ref "IC2") (pin "15") (pinfunction "IOA14_15") (pintype "bidirectional"))
    )
    (net (code "73") (name "unconnected-(IC2-IOB0-Pad18)") (class "Default")
      (node (ref "IC2") (pin "18") (pinfunction "IOB0_18") (pintype "bidirectional"))
    )
    (net (code "74") (name "unconnected-(IC2-IOB1-Pad19)") (class "Default")
      (node (ref "IC2") (pin "19") (pinfunction "IOB1_19") (pintype "bidirectional"))
    )
    (net (code "75") (name "unconnected-(IC2-IOB2-Pad20)") (class "Default")
      (node (ref "IC2") (pin "20") (pinfunction "IOB2_20") (pintype "bidirectional"))
    )
    (net (code "76") (name "unconnected-(IC2-IOB3-Pad21)") (class "Default")
      (node (ref "IC2") (pin "21") (pinfunction "IOB3_21") (pintype "bidirectional"))
    )
    (net (code "77") (name "unconnected-(IC2-IOB4-Pad22)") (class "Default")
      (node (ref "IC2") (pin "22") (pinfunction "IOB4_22") (pintype "bidirectional"))
    )
    (net (code "78") (name "unconnected-(IC2-IOB5-Pad24)") (class "Default")
      (node (ref "IC2") (pin "24") (pinfunction "IOB5_24") (pintype "bidirectional"))
    )
    (net (code "79") (name "unconnected-(IC2-IOB6-Pad25)") (class "Default")
      (node (ref "IC2") (pin "25") (pinfunction "IOB6_25") (pintype "bidirectional"))
    )
    (net (code "80") (name "unconnected-(IC2-IOB7-Pad26)") (class "Default")
      (node (ref "IC2") (pin "26") (pinfunction "IOB7_26") (pintype "bidirectional"))
    )
    (net (code "81") (name "unconnected-(IC2-IOB8-Pad29)") (class "Default")
      (node (ref "IC2") (pin "29") (pinfunction "IOB8_29") (pintype "bidirectional"))
    )
    (net (code "82") (name "unconnected-(IC2-IOB9-Pad30)") (class "Default")
      (node (ref "IC2") (pin "30") (pinfunction "IOB9_30") (pintype "bidirectional"))
    )
    (net (code "83") (name "unconnected-(IC3A-~{Q}-Pad4)") (class "Default")
      (node (ref "IC3") (pin "4") (pinfunction "~{Q}_4") (pintype "output"))
    )
    (net (code "84") (name "unconnected-(IC3B-~{Q}-Pad12)") (class "Default")
      (node (ref "IC3") (pin "12") (pinfunction "~{Q}_12") (pintype "output"))
    )
    (net (code "85") (name "unconnected-(IC11-Pad5)") (class "Default")
      (node (ref "IC11") (pin "5") (pinfunction "5_5") (pintype "no_connect"))
    )
    (net (code "86") (name "unconnected-(IC11-Pad7)") (class "Default")
      (node (ref "IC11") (pin "7") (pinfunction "7_7") (pintype "bidirectional"))
    )
    (net (code "87") (name "unconnected-(IC11-Pad9)") (class "Default")
      (node (ref "IC11") (pin "9") (pinfunction "9_9") (pintype "no_connect"))
    )
    (net (code "88") (name "unconnected-(IC11-Pad13)") (class "Default")
      (node (ref "IC11") (pin "13") (pinfunction "13_13") (pintype "no_connect"))
    )
    (net (code "89") (name "unconnected-(IC11-Pad15)") (class "Default")
      (node (ref "IC11") (pin "15") (pinfunction "15_15") (pintype "no_connect"))
    )
    (net (code "90") (name "unconnected-(IC11-Pad16)") (class "Default")
      (node (ref "IC11") (pin "16") (pinfunction "16_16") (pintype "no_connect"))
    )
    (net (code "91") (name "unconnected-(IC11-Pad17)") (class "Default")
      (node (ref "IC11") (pin "17") (pinfunction "17_17") (pintype "no_connect"))
    )
    (net (code "92") (name "unconnected-(IC11-Pad18)") (class "Default")
      (node (ref "IC11") (pin "18") (pinfunction "18_18") (pintype "no_connect"))
    )
    (net (code "93") (name "unconnected-(R72-E-Pad3)") (class "Default")
      (node (ref "R72") (pin "3") (pinfunction "E_3") (pintype "passive"))
    )
  )
)
